# Driver.net
KiCad netlist of a schematic drawn in Altium Designer
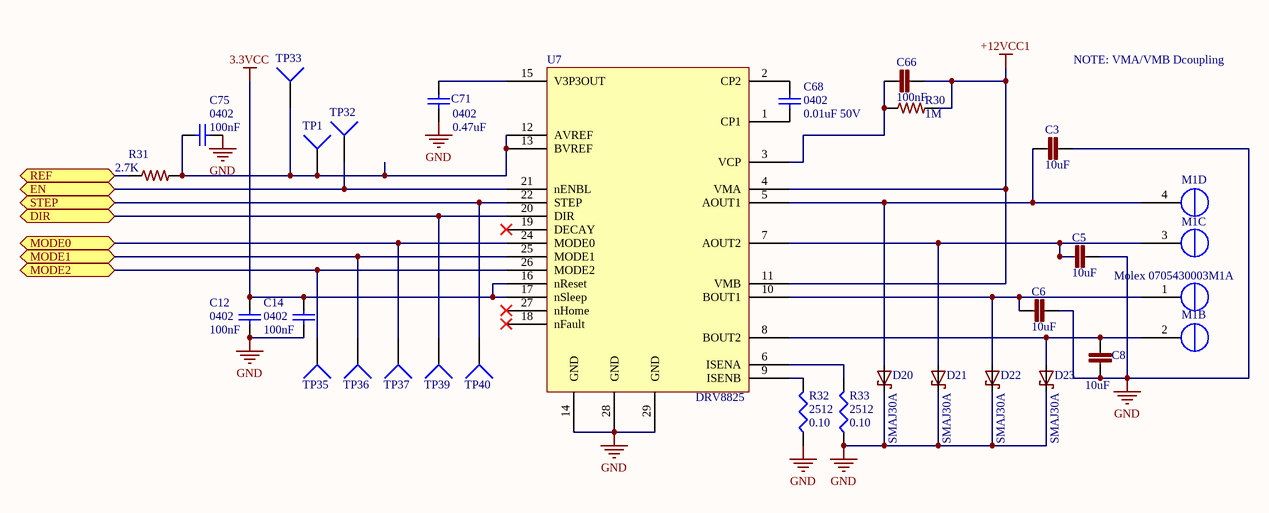
[diagram p0: Driver.SchDoc]

(export (version "E")
  (design (tool "Eeschema 10.0.6"))
  (components
    (comp (ref "C3")
      (value "10uF")
      (footprint "C0603")
      (description "CAP CER 0603 1uF 10V Y5V")
      (fields
        (field (name "MANUFACTURERPARTNUMBER") "CC0603ZRY5V6BB105")
        (field (name "PUBLISHER") "UltiMachine")
      )
      (libsource (lib "Tigershark3D") (part "CC0603ZRY5V6BB105"))
    )
    (comp (ref "C5")
      (value "10uF")
      (footprint "C0603")
      (description "CAP CER 0603 1uF 10V Y5V")
      (fields
        (field (name "MANUFACTURERPARTNUMBER") "CC0603ZRY5V6BB105")
        (field (name "PUBLISHER") "UltiMachine")
      )
      (libsource (lib "Tigershark3D") (part "CC0603ZRY5V6BB105"))
    )
    (comp (ref "C6")
      (value "10uF")
      (footprint "C0603")
      (description "CAP CER 0603 1uF 10V Y5V")
      (fields
        (field (name "MANUFACTURERPARTNUMBER") "CC0603ZRY5V6BB105")
        (field (name "PUBLISHER") "UltiMachine")
      )
      (libsource (lib "Tigershark3D") (part "CC0603ZRY5V6BB105"))
    )
    (comp (ref "C8")
      (value "10uF")
      (footprint "C0603")
      (description "CAP CER 0603 1uF 10V Y5V")
      (fields
        (field (name "MANUFACTURERPARTNUMBER") "CC0603ZRY5V6BB105")
        (field (name "PUBLISHER") "UltiMachine")
      )
      (libsource (lib "") (part "CC0603ZRY5V6BB105_1"))
    )
    (comp (ref "C12")
      (value "100nF")
      (footprint "C0402")
      (description "Capacitor (Semiconductor SIM Model)")
      (fields
        (field (name "MFR PART #") "GRM155R71C104KA88D")
        (field (name "MFR") "Murata")
        (field (name "PACKAGEREFERENCE") "0402")
        (field (name "PUBLISHER") "Ultimachine")
      )
      (libsource (lib "Tigershark3D") (part "100nF C0402 - GRM155R71C104KA88D"))
    )
    (comp (ref "C14")
      (value "100nF")
      (footprint "C0402")
      (description "Capacitor (Semiconductor SIM Model)")
      (fields
        (field (name "MFR PART #") "GRM155R71C104KA88D")
        (field (name "MFR") "Murata")
        (field (name "PACKAGEREFERENCE") "0402")
        (field (name "PUBLISHER") "Ultimachine")
      )
      (libsource (lib "Tigershark3D") (part "100nF C0402 - GRM155R71C104KA88D"))
    )
    (comp (ref "C66")
      (value "100nF")
      (footprint "C0603")
      (description "CAP CER 0603 100nF 50V 10% X7R")
      (fields
        (field (name "MANUFACTURERPARTNUMBER") "C0603C104K5RACTU")
        (field (name "PUBLISHER") "UltiMachine")
      )
      (libsource (lib "3Delight") (part "C0603C104K5RACTU"))
    )
    (comp (ref "C68")
      (value "0.01uF 50V")
      (footprint "C0402")
      (description "CAP CER 10000PF 50V X7R 0402")
      (fields
        (field (name "MFR PART #") "GRM155R71H103JA88D")
        (field (name "MFR") "Murata")
        (field (name "PACKAGEREFERENCE") "0402")
        (field (name "PUBLISHER") "Ultimachine")
      )
      (libsource (lib "Tigershark3D") (part "GRM155R71H103JA88D"))
    )
    (comp (ref "C71")
      (value "0.47uF")
      (footprint "C0402")
      (description "0.47uF 6.3v C0402 - GRM155R60J474KE19D")
      (fields
        (field (name "MFR PART #") "GRM155R60J474KE19D")
        (field (name "MFR") "Murata")
        (field (name "PACKAGEREFERENCE") "0402")
        (field (name "PUBLISHER") "Ultimachine")
      )
      (libsource (lib "Tigershark3D") (part "GRM155R60J474KE19D"))
    )
    (comp (ref "C75")
      (value "100nF")
      (footprint "C0402")
      (description "Capacitor (Semiconductor SIM Model)")
      (fields
        (field (name "MFR PART #") "GRM155R71C104KA88D")
        (field (name "MFR") "Murata")
        (field (name "PACKAGEREFERENCE") "0402")
        (field (name "PUBLISHER") "Ultimachine")
      )
      (libsource (lib "Tigershark3D") (part "100nF C0402 - GRM155R71C104KA88D"))
    )
    (comp (ref "D20")
      (value "SMAJ30A")
      (footprint "SMA-SM")
      (description "DIODE TVS 30V SMA")
      (fields (field (name "PUBLISHER") "UltiMachine"))
      (libsource (lib "Tigershark3D") (part "SMAJ30A"))
    )
    (comp (ref "D21")
      (value "SMAJ30A")
      (footprint "SMA-SM")
      (description "DIODE TVS 30V SMA")
      (fields (field (name "PUBLISHER") "UltiMachine"))
      (libsource (lib "Tigershark3D") (part "SMAJ30A"))
    )
    (comp (ref "D22")
      (value "SMAJ30A")
      (footprint "SMA-SM")
      (description "DIODE TVS 30V SMA")
      (fields (field (name "PUBLISHER") "UltiMachine"))
      (libsource (lib "Tigershark3D") (part "SMAJ30A"))
    )
    (comp (ref "D23")
      (value "SMAJ30A")
      (footprint "SMA-SM")
      (description "DIODE TVS 30V SMA")
      (fields (field (name "PUBLISHER") "UltiMachine"))
      (libsource (lib "Tigershark3D") (part "SMAJ30A"))
    )
    (comp (ref "M1")
      (value "Molex 0705430003")
      (footprint "4POL254")
      (description "Molex 4 Pin Clip Connector")
      (libsource (lib "ZMBo Schematic Library") (part "Molex 0705430003 Alt"))
    )
    (comp (ref "R30")
      (value "1M")
      (footprint "R0402")
      (description "RES 0402 1M 100mW 5%")
      (fields (field (name "MANUFACTURERPARTNUMBER") "ERJ2GEJ105X") (field (name "PUBLISHER") "UltiMachine"))
      (libsource (lib "Tigershark3D") (part "ERJ2GEJ105X"))
    )
    (comp (ref "R31")
      (value "2.7K")
      (footprint "R0402")
      (description "RES SMD 2.7K OHM 1% 1/10W 0402")
      (fields
        (field (name "MANUFACTURER") "Panasonic")
        (field (name "MANUFACTURERPARTNUMBER") "ERJ2GEJ105X")
        (field (name "PUBLISHER") "Adam")
      )
      (libsource (lib "Tigershark3D") (part "ERJ-2RKF2701X"))
    )
    (comp (ref "R32")
      (value "2512")
      (footprint "2512R-0.55")
      (description "RES SMD 0.1 OHM 1% 2W 2512")
      (fields (field (name "MFR") "Stackpole ELectronics Inc") (field (name "ALTIUM_VALUE") "0.10"))
      (libsource (lib "Tigershark3D") (part "CSRN2512FTR100"))
    )
    (comp (ref "R33")
      (value "2512")
      (footprint "2512R-0.55")
      (description "RES SMD 0.1 OHM 1% 2W 2512")
      (fields (field (name "MFR") "Stackpole ELectronics Inc") (field (name "ALTIUM_VALUE") "0.10"))
      (libsource (lib "Tigershark3D") (part "CSRN2512FTR100"))
    )
    (comp (ref "TP1")
      (value "TP4")
      (footprint "TP-2")
      (description "Socket")
      (fields (field (name "PUBLISHER") "Altium Limited"))
      (libsource (lib "ZMBo Schematic Library") (part "Socket"))
    )
    (comp (ref "TP32")
      (value "TP4")
      (footprint "TP-2")
      (description "Socket")
      (fields (field (name "PUBLISHER") "Altium Limited"))
      (libsource (lib "ZMBo Schematic Library") (part "Socket"))
    )
    (comp (ref "TP33")
      (value "TP4")
      (footprint "TP-2")
      (description "Socket")
      (fields (field (name "PUBLISHER") "Altium Limited"))
      (libsource (lib "ZMBo Schematic Library") (part "Socket"))
    )
    (comp (ref "TP35")
      (value "TP4")
      (footprint "TP-2")
      (description "Socket")
      (fields (field (name "PUBLISHER") "Altium Limited"))
      (libsource (lib "ZMBo Schematic Library") (part "Socket"))
    )
    (comp (ref "TP36")
      (value "TP4")
      (footprint "TP-2")
      (description "Socket")
      (fields (field (name "PUBLISHER") "Altium Limited"))
      (libsource (lib "ZMBo Schematic Library") (part "Socket"))
    )
    (comp (ref "TP37")
      (value "TP4")
      (footprint "TP-2")
      (description "Socket")
      (fields (field (name "PUBLISHER") "Altium Limited"))
      (libsource (lib "ZMBo Schematic Library") (part "Socket"))
    )
    (comp (ref "TP39")
      (value "TP4")
      (footprint "TP-2")
      (description "Socket")
      (fields (field (name "PUBLISHER") "Altium Limited"))
      (libsource (lib "ZMBo Schematic Library") (part "Socket"))
    )
    (comp (ref "TP40")
      (value "TP4")
      (footprint "TP-2")
      (description "Socket")
      (fields (field (name "PUBLISHER") "Altium Limited"))
      (libsource (lib "ZMBo Schematic Library") (part "Socket"))
    )
    (comp (ref "U7")
      (value "DRV8825")
      (footprint "DRV8825")
      (description "DRV8825 Ti Stepper Driver")
      (libsource (lib "ZMBo Schematic Library") (part "DRV8825"))
    )
  )
  (nets
    (net (code "1") (name "+12VCC1") (class "Default")
      (node (ref "C66") (pin "2") (pinfunction "2_2") (pintype "passive"))
      (node (ref "R30") (pin "2") (pinfunction "2_2") (pintype "passive"))
      (node (ref "U7") (pin "11") (pinfunction "VMB_11") (pintype "passive"))
      (node (ref "U7") (pin "4") (pinfunction "VMA_4") (pintype "passive"))
    )
    (net (code "2") (name "/DIR") (class "Default")
      (node (ref "TP39") (pin "1") (pinfunction "1_1") (pintype "passive"))
      (node (ref "U7") (pin "20") (pinfunction "DIR_20") (pintype "passive"))
    )
    (net (code "3") (name "/EN") (class "Default")
      (node (ref "TP32") (pin "1") (pinfunction "1_1") (pintype "passive"))
      (node (ref "U7") (pin "21") (pinfunction "nENBL_21") (pintype "passive"))
    )
    (net (code "4") (name "/MODE0") (class "Default")
      (node (ref "TP37") (pin "1") (pinfunction "1_1") (pintype "passive"))
      (node (ref "U7") (pin "24") (pinfunction "MODE0_24") (pintype "passive"))
    )
    (net (code "5") (name "/MODE1") (class "Default")
      (node (ref "TP36") (pin "1") (pinfunction "1_1") (pintype "passive"))
      (node (ref "U7") (pin "25") (pinfunction "MODE1_25") (pintype "passive"))
    )
    (net (code "6") (name "/MODE2") (class "Default")
      (node (ref "TP35") (pin "1") (pinfunction "1_1") (pintype "passive"))
      (node (ref "U7") (pin "26") (pinfunction "MODE2_26") (pintype "passive"))
    )
    (net (code "7") (name "/REF") (class "Default")
      (node (ref "R31") (pin "1") (pinfunction "1_1") (pintype "passive"))
    )
    (net (code "8") (name "/STEP") (class "Default")
      (node (ref "TP40") (pin "1") (pinfunction "1_1") (pintype "passive"))
      (node (ref "U7") (pin "22") (pinfunction "STEP_22") (pintype "passive"))
    )
    (net (code "9") (name "3.3VCC") (class "Default")
      (node (ref "C12") (pin "2") (pinfunction "2_2") (pintype "passive"))
      (node (ref "C14") (pin "2") (pinfunction "2_2") (pintype "passive"))
      (node (ref "U7") (pin "16") (pinfunction "nReset_16") (pintype "passive"))
      (node (ref "U7") (pin "17") (pinfunction "nSleep_17") (pintype "passive"))
    )
    (net (code "10") (name "GND") (class "Default")
      (node (ref "C12") (pin "1") (pinfunction "1_1") (pintype "passive"))
      (node (ref "C14") (pin "1") (pinfunction "1_1") (pintype "passive"))
      (node (ref "C3") (pin "2") (pinfunction "2_2") (pintype "passive"))
      (node (ref "C5") (pin "2") (pinfunction "2_2") (pintype "passive"))
      (node (ref "C6") (pin "2") (pinfunction "2_2") (pintype "passive"))
      (node (ref "C71") (pin "1") (pinfunction "1_1") (pintype "passive"))
      (node (ref "C75") (pin "1") (pinfunction "1_1") (pintype "passive"))
      (node (ref "C8") (pin "2") (pinfunction "2_2") (pintype "passive"))
      (node (ref "D20") (pin "C") (pinfunction "C_C") (pintype "passive"))
      (node (ref "D21") (pin "C") (pinfunction "C_C") (pintype "passive"))
      (node (ref "D22") (pin "C") (pinfunction "C_C") (pintype "passive"))
      (node (ref "D23") (pin "C") (pinfunction "C_C") (pintype "passive"))
      (node (ref "R32") (pin "1") (pinfunction "1_1") (pintype "passive"))
      (node (ref "R33") (pin "1") (pinfunction "1_1") (pintype "passive"))
      (node (ref "U7") (pin "14") (pinfunction "GND_14") (pintype "passive"))
      (node (ref "U7") (pin "28") (pinfunction "GND_28") (pintype "passive"))
      (node (ref "U7") (pin "29") (pinfunction "GND_29") (pintype "passive"))
    )
    (net (code "11") (name "Net-(M1A-OUT2B)") (class "Default")
      (node (ref "C6") (pin "1") (pinfunction "1_1") (pintype "passive"))
      (node (ref "D22") (pin "A") (pinfunction "A_A") (pintype "passive"))
      (node (ref "M1") (pin "1") (pinfunction "OUT2B_1") (pintype "passive"))
      (node (ref "U7") (pin "10") (pinfunction "BOUT1_10") (pintype "passive"))
    )
    (net (code "12") (name "Net-(M1B-OUT2A)") (class "Default")
      (node (ref "C8") (pin "1") (pinfunction "1_1") (pintype "passive"))
      (node (ref "D23") (pin "A") (pinfunction "A_A") (pintype "passive"))
      (node (ref "M1") (pin "2") (pinfunction "OUT2A_2") (pintype "passive"))
      (node (ref "U7") (pin "8") (pinfunction "BOUT2_8") (pintype "passive"))
    )
    (net (code "13") (name "Net-(M1C-OUT1A)") (class "Default")
      (node (ref "C5") (pin "1") (pinfunction "1_1") (pintype "passive"))
      (node (ref "D21") (pin "A") (pinfunction "A_A") (pintype "passive"))
      (node (ref "M1") (pin "3") (pinfunction "OUT1A_3") (pintype "passive"))
      (node (ref "U7") (pin "7") (pinfunction "AOUT2_7") (pintype "passive"))
    )
    (net (code "14") (name "Net-(M1D-OUT1B)") (class "Default")
      (node (ref "C3") (pin "1") (pinfunction "1_1") (pintype "passive"))
      (node (ref "D20") (pin "A") (pinfunction "A_A") (pintype "passive"))
      (node (ref "M1") (pin "4") (pinfunction "OUT1B_4") (pintype "passive"))
      (node (ref "U7") (pin "5") (pinfunction "AOUT1_5") (pintype "passive"))
    )
    (net (code "15") (name "Net-(U7-AVREF)") (class "Default")
      (node (ref "C75") (pin "2") (pinfunction "2_2") (pintype "passive"))
      (node (ref "R31") (pin "2") (pinfunction "2_2") (pintype "passive"))
      (node (ref "TP1") (pin "1") (pinfunction "1_1") (pintype "passive"))
      (node (ref "TP33") (pin "1") (pinfunction "1_1") (pintype "passive"))
      (node (ref "U7") (pin "12") (pinfunction "AVREF_12") (pintype "passive"))
      (node (ref "U7") (pin "13") (pinfunction "BVREF_13") (pintype "passive"))
    )
    (net (code "16") (name "Net-(U7-CP1)") (class "Default")
      (node (ref "C68") (pin "1") (pinfunction "1_1") (pintype "passive"))
      (node (ref "U7") (pin "1") (pinfunction "CP1_1") (pintype "passive"))
    )
    (net (code "17") (name "Net-(U7-CP2)") (class "Default")
      (node (ref "C68") (pin "2") (pinfunction "2_2") (pintype "passive"))
      (node (ref "U7") (pin "2") (pinfunction "CP2_2") (pintype "passive"))
    )
    (net (code "18") (name "Net-(U7-ISENA)") (class "Default")
      (node (ref "R33") (pin "2") (pinfunction "2_2") (pintype "passive"))
      (node (ref "U7") (pin "6") (pinfunction "ISENA_6") (pintype "passive"))
    )
    (net (code "19") (name "Net-(U7-ISENB)") (class "Default")
      (node (ref "R32") (pin "2") (pinfunction "2_2") (pintype "passive"))
      (node (ref "U7") (pin "9") (pinfunction "ISENB_9") (pintype "passive"))
    )
    (net (code "20") (name "Net-(U7-V3P3OUT)") (class "Default")
      (node (ref "C71") (pin "2") (pinfunction "2_2") (pintype "passive"))
      (node (ref "U7") (pin "15") (pinfunction "V3P3OUT_15") (pintype "passive"))
    )
    (net (code "21") (name "Net-(U7-VCP)") (class "Default")
      (node (ref "C66") (pin "1") (pinfunction "1_1") (pintype "passive"))
      (node (ref "R30") (pin "1") (pinfunction "1_1") (pintype "passive"))
      (node (ref "U7") (pin "3") (pinfunction "VCP_3") (pintype "passive"))
    )
    (net (code "22") (name "unconnected-(U7-DECAY-Pad19)") (class "Default")
      (node (ref "U7") (pin "19") (pinfunction "DECAY_19") (pintype "passive+no_connect"))
    )
    (net (code "23") (name "unconnected-(U7-NC-Pad23)") (class "Default")
      (node (ref "U7") (pin "23") (pinfunction "NC_23") (pintype "passive"))
    )
    (net (code "24") (name "unconnected-(U7-nFault-Pad18)") (class "Default")
      (node (ref "U7") (pin "18") (pinfunction "nFault_18") (pintype "passive+no_connect"))
    )
    (net (code "25") (name "unconnected-(U7-nHome-Pad27)") (class "Default")
      (node (ref "U7") (pin "27") (pinfunction "nHome_27") (pintype "passive+no_connect"))
    )
  )
)
